# isolated_io_booster_pack.net
KiCad netlist of a schematic drawn in EAGLE
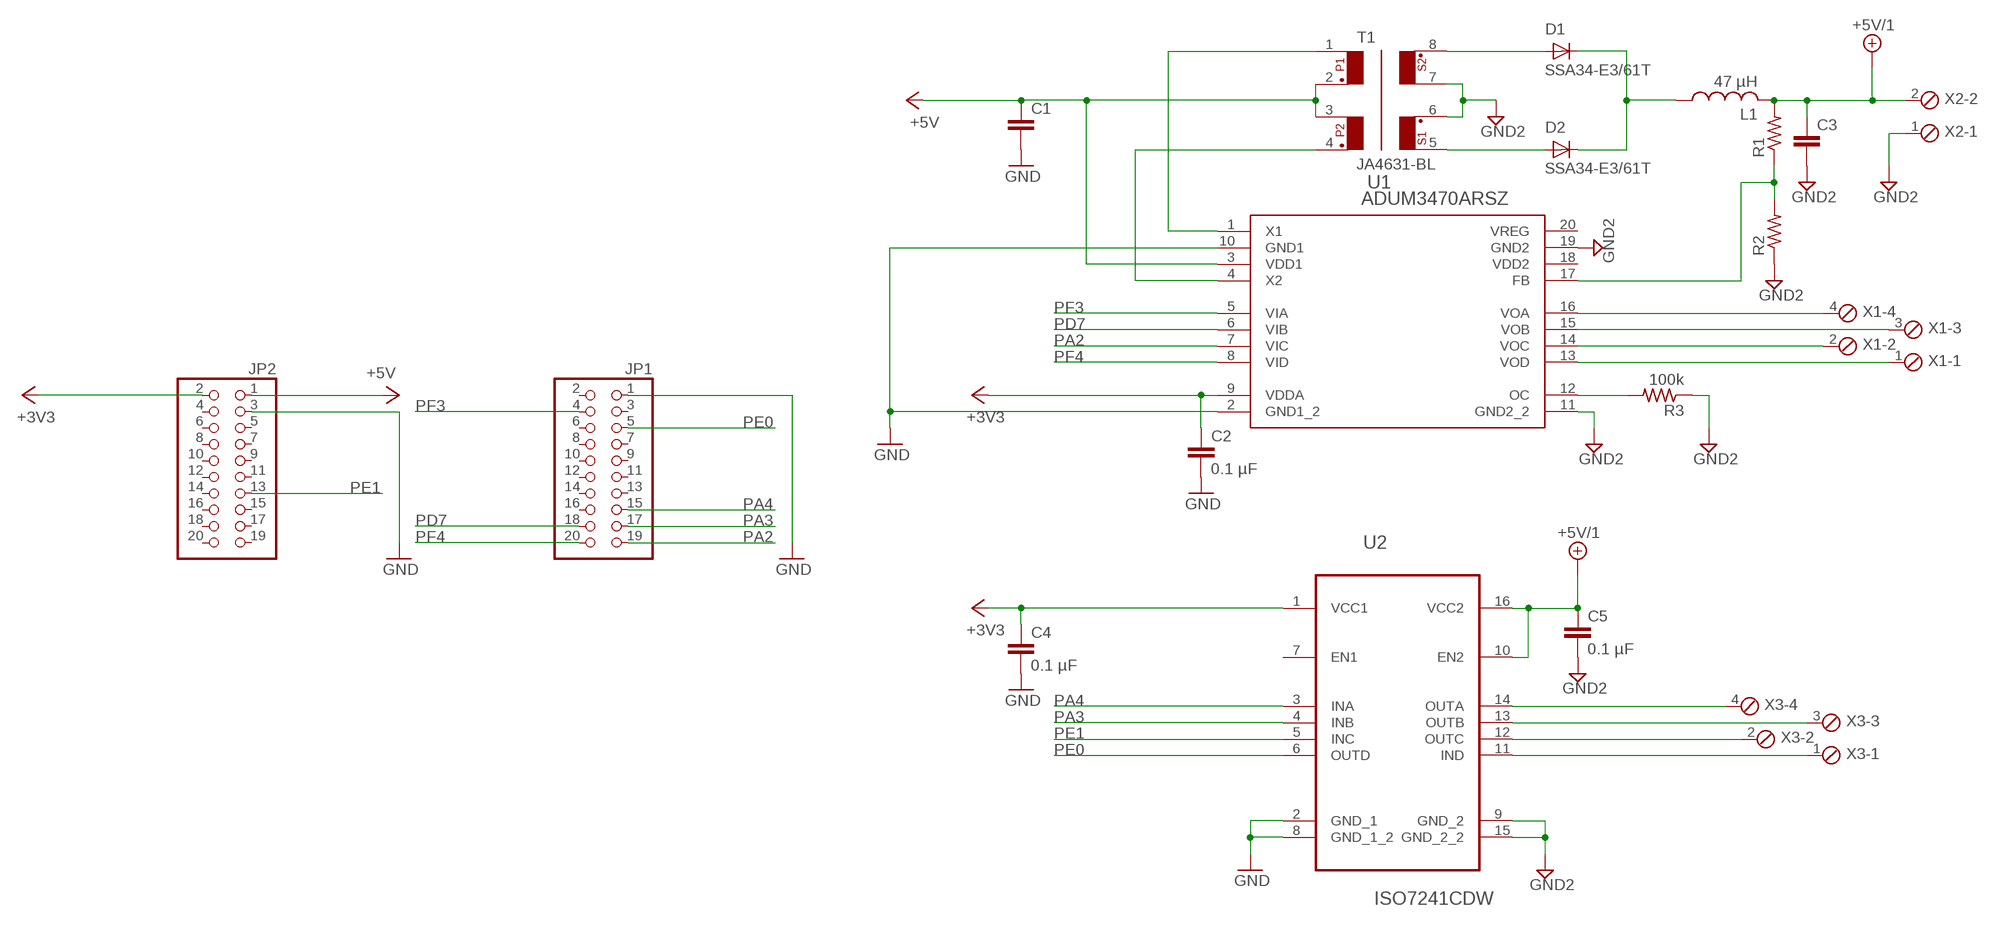
[diagram p0: schematic, sheet 1]

(export (version "E")
  (design (tool "Eeschema 10.0.6"))
  (components
    (comp (ref "C1")
      (value "C-EUC1210")
      (footprint "eagle-import:C1210")
      (libsource (lib "eagle-import") (part "C-EUC1210"))
    )
    (comp (ref "C2")
      (value "0.1 µF")
      (footprint "eagle-import:C0805")
      (libsource (lib "eagle-import") (part "C-EUC0805"))
    )
    (comp (ref "C3")
      (value "C-EUC1210")
      (footprint "eagle-import:C1210")
      (libsource (lib "eagle-import") (part "C-EUC1210"))
    )
    (comp (ref "C4")
      (value "0.1 µF")
      (footprint "eagle-import:C0805")
      (libsource (lib "eagle-import") (part "C-EUC0805"))
    )
    (comp (ref "C5")
      (value "0.1 µF")
      (footprint "eagle-import:C0805")
      (libsource (lib "eagle-import") (part "C-EUC0805"))
    )
    (comp (ref "D1")
      (value "SSA34-E3/61T")
      (footprint "eagle-import:SMA-DO214AC")
      (libsource (lib "eagle-import") (part "GF1"))
    )
    (comp (ref "D2")
      (value "SSA34-E3/61T")
      (footprint "eagle-import:SMA-DO214AC")
      (libsource (lib "eagle-import") (part "GF1"))
    )
    (comp (ref "JP1")
      (value "PINHD-2X10")
      (footprint "eagle-import:2X10")
      (libsource (lib "eagle-import") (part "PINHD-2X10"))
    )
    (comp (ref "JP2")
      (value "PINHD-2X10")
      (footprint "eagle-import:2X10")
      (libsource (lib "eagle-import") (part "PINHD-2X10"))
    )
    (comp (ref "L1")
      (value "47 µH")
      (footprint "eagle-import:LPS5030")
      (libsource (lib "eagle-import") (part "L-USLPS5030"))
    )
    (comp (ref "R1")
      (value "R-US_R0805")
      (footprint "eagle-import:R0805")
      (libsource (lib "eagle-import") (part "R-US_R0805"))
    )
    (comp (ref "R2")
      (value "R-US_R0805")
      (footprint "eagle-import:R0805")
      (libsource (lib "eagle-import") (part "R-US_R0805"))
    )
    (comp (ref "R3")
      (value "100k")
      (footprint "eagle-import:R0805")
      (libsource (lib "eagle-import") (part "R-US_R0805"))
    )
    (comp (ref "T1")
      (value "JA4631-BL")
      (footprint "eagle-import:JA4631-BL")
      (libsource (lib "eagle-import") (part "JA4631-BL"))
    )
    (comp (ref "U1")
      (value "ADUM3470ARSZ")
      (footprint "eagle-import:RS_20")
      (libsource (lib "eagle-import") (part "ADUM3470ARSZ"))
    )
    (comp (ref "U2")
      (value "ISO7241CDW")
      (footprint "eagle-import:SOIC127P1030X265-16N")
      (libsource (lib "eagle-import") (part "ISO7241CDW"))
    )
    (comp (ref "X1")
      (value "MPT4")
      (footprint "eagle-import:4POL254")
      (libsource (lib "eagle-import") (part "MPT4"))
    )
    (comp (ref "X2")
      (value "MPT2")
      (footprint "eagle-import:2POL254")
      (libsource (lib "eagle-import") (part "MPT2"))
    )
    (comp (ref "X3")
      (value "MPT4")
      (footprint "eagle-import:4POL254")
      (libsource (lib "eagle-import") (part "MPT4"))
    )
  )
  (nets
    (net (code "1") (name "+3V3") (class "Default")
      (node (ref "C2") (pin "1") (pinfunction "1_1") (pintype "passive"))
      (node (ref "C4") (pin "1") (pinfunction "1_1") (pintype "passive"))
      (node (ref "JP2") (pin "2") (pinfunction "2_2") (pintype "passive"))
      (node (ref "U1") (pin "9") (pinfunction "VDDA_9") (pintype "passive"))
      (node (ref "U2") (pin "1") (pinfunction "VCC1_1") (pintype "power_in"))
    )
    (net (code "2") (name "+5V") (class "Default")
      (node (ref "C1") (pin "1") (pinfunction "1_1") (pintype "passive"))
      (node (ref "JP2") (pin "1") (pinfunction "1_1") (pintype "passive"))
      (node (ref "T1") (pin "2") (pinfunction "2_2") (pintype "passive"))
      (node (ref "T1") (pin "3") (pinfunction "3_3") (pintype "passive"))
      (node (ref "U1") (pin "3") (pinfunction "VDD1_3") (pintype "passive"))
    )
    (net (code "3") (name "+5V{slash}1") (class "Default")
      (node (ref "C3") (pin "1") (pinfunction "1_1") (pintype "passive"))
      (node (ref "C5") (pin "1") (pinfunction "1_1") (pintype "passive"))
      (node (ref "L1") (pin "2") (pinfunction "2_2") (pintype "passive"))
      (node (ref "R1") (pin "2") (pinfunction "2_2") (pintype "passive"))
      (node (ref "U2") (pin "10") (pinfunction "EN2_10") (pintype "input"))
      (node (ref "U2") (pin "16") (pinfunction "VCC2_16") (pintype "power_in"))
      (node (ref "X2") (pin "2") (pinfunction "1_2") (pintype "passive"))
    )
    (net (code "4") (name "/PA2") (class "Default")
      (node (ref "JP1") (pin "19") (pinfunction "19_19") (pintype "passive"))
      (node (ref "U1") (pin "7") (pinfunction "VIC_7") (pintype "passive"))
    )
    (net (code "5") (name "/PA3") (class "Default")
      (node (ref "JP1") (pin "17") (pinfunction "17_17") (pintype "passive"))
      (node (ref "U2") (pin "4") (pinfunction "INB_4") (pintype "input"))
    )
    (net (code "6") (name "/PA4") (class "Default")
      (node (ref "JP1") (pin "15") (pinfunction "15_15") (pintype "passive"))
      (node (ref "U2") (pin "3") (pinfunction "INA_3") (pintype "input"))
    )
    (net (code "7") (name "/PD7") (class "Default")
      (node (ref "JP1") (pin "18") (pinfunction "18_18") (pintype "passive"))
      (node (ref "U1") (pin "6") (pinfunction "VIB_6") (pintype "passive"))
    )
    (net (code "8") (name "/PE0") (class "Default")
      (node (ref "JP1") (pin "5") (pinfunction "5_5") (pintype "passive"))
      (node (ref "U2") (pin "6") (pinfunction "OUTD_6") (pintype "output"))
    )
    (net (code "9") (name "/PE1") (class "Default")
      (node (ref "JP2") (pin "13") (pinfunction "13_13") (pintype "passive"))
      (node (ref "U2") (pin "5") (pinfunction "INC_5") (pintype "input"))
    )
    (net (code "10") (name "/PF3") (class "Default")
      (node (ref "JP1") (pin "4") (pinfunction "4_4") (pintype "passive"))
      (node (ref "U1") (pin "5") (pinfunction "VIA_5") (pintype "passive"))
    )
    (net (code "11") (name "/PF4") (class "Default")
      (node (ref "JP1") (pin "20") (pinfunction "20_20") (pintype "passive"))
      (node (ref "U1") (pin "8") (pinfunction "VID_8") (pintype "passive"))
    )
    (net (code "12") (name "GND") (class "Default")
      (node (ref "C1") (pin "2") (pinfunction "2_2") (pintype "passive"))
      (node (ref "C2") (pin "2") (pinfunction "2_2") (pintype "passive"))
      (node (ref "C4") (pin "2") (pinfunction "2_2") (pintype "passive"))
      (node (ref "JP1") (pin "1") (pinfunction "1_1") (pintype "passive"))
      (node (ref "JP2") (pin "3") (pinfunction "3_3") (pintype "passive"))
      (node (ref "U1") (pin "10") (pinfunction "GND1_10") (pintype "passive"))
      (node (ref "U1") (pin "2") (pinfunction "GND1_2_2") (pintype "passive"))
      (node (ref "U2") (pin "2") (pinfunction "GND_1_2") (pintype "passive"))
      (node (ref "U2") (pin "8") (pinfunction "GND_1_2_8") (pintype "passive"))
    )
    (net (code "13") (name "GND2") (class "Default")
      (node (ref "C3") (pin "2") (pinfunction "2_2") (pintype "passive"))
      (node (ref "C5") (pin "2") (pinfunction "2_2") (pintype "passive"))
      (node (ref "R2") (pin "1") (pinfunction "1_1") (pintype "passive"))
      (node (ref "R3") (pin "1") (pinfunction "1_1") (pintype "passive"))
      (node (ref "T1") (pin "6") (pinfunction "6_6") (pintype "passive"))
      (node (ref "T1") (pin "7") (pinfunction "7_7") (pintype "passive"))
      (node (ref "U1") (pin "11") (pinfunction "GND2_2_11") (pintype "passive"))
      (node (ref "U1") (pin "19") (pinfunction "GND2_19") (pintype "passive"))
      (node (ref "U2") (pin "15") (pinfunction "GND_2_2_15") (pintype "passive"))
      (node (ref "U2") (pin "9") (pinfunction "GND_2_9") (pintype "passive"))
      (node (ref "X2") (pin "1") (pinfunction "1_1") (pintype "passive"))
    )
    (net (code "14") (name "Net-(D1-C)") (class "Default")
      (node (ref "D1") (pin "K") (pinfunction "C_K") (pintype "passive"))
      (node (ref "D2") (pin "K") (pinfunction "C_K") (pintype "passive"))
      (node (ref "L1") (pin "1") (pinfunction "1_1") (pintype "passive"))
    )
    (net (code "15") (name "Net-(D1-PadA)") (class "Default")
      (node (ref "D1") (pin "A") (pinfunction "A_A") (pintype "passive"))
      (node (ref "T1") (pin "8") (pinfunction "8_8") (pintype "passive"))
    )
    (net (code "16") (name "Net-(D2-PadA)") (class "Default")
      (node (ref "D2") (pin "A") (pinfunction "A_A") (pintype "passive"))
      (node (ref "T1") (pin "5") (pinfunction "5_5") (pintype "passive"))
    )
    (net (code "17") (name "Net-(U1-FB)") (class "Default")
      (node (ref "R1") (pin "1") (pinfunction "1_1") (pintype "passive"))
      (node (ref "R2") (pin "2") (pinfunction "2_2") (pintype "passive"))
      (node (ref "U1") (pin "17") (pinfunction "FB_17") (pintype "passive"))
    )
    (net (code "18") (name "Net-(U1-OC)") (class "Default")
      (node (ref "R3") (pin "2") (pinfunction "2_2") (pintype "passive"))
      (node (ref "U1") (pin "12") (pinfunction "OC_12") (pintype "passive"))
    )
    (net (code "19") (name "Net-(U1-VOA)") (class "Default")
      (node (ref "U1") (pin "16") (pinfunction "VOA_16") (pintype "passive"))
      (node (ref "X1") (pin "4") (pinfunction "1_4") (pintype "passive"))
    )
    (net (code "20") (name "Net-(U1-VOB)") (class "Default")
      (node (ref "U1") (pin "15") (pinfunction "VOB_15") (pintype "passive"))
      (node (ref "X1") (pin "3") (pinfunction "1_3") (pintype "passive"))
    )
    (net (code "21") (name "Net-(U1-VOC)") (class "Default")
      (node (ref "U1") (pin "14") (pinfunction "VOC_14") (pintype "passive"))
      (node (ref "X1") (pin "2") (pinfunction "1_2") (pintype "passive"))
    )
    (net (code "22") (name "Net-(U1-VOD)") (class "Default")
      (node (ref "U1") (pin "13") (pinfunction "VOD_13") (pintype "passive"))
      (node (ref "X1") (pin "1") (pinfunction "1_1") (pintype "passive"))
    )
    (net (code "23") (name "Net-(U1-X1)") (class "Default")
      (node (ref "T1") (pin "1") (pinfunction "1_1") (pintype "passive"))
      (node (ref "U1") (pin "1") (pinfunction "X1_1") (pintype "passive"))
    )
    (net (code "24") (name "Net-(U1-X2)") (class "Default")
      (node (ref "T1") (pin "4") (pinfunction "4_4") (pintype "passive"))
      (node (ref "U1") (pin "4") (pinfunction "X2_4") (pintype "passive"))
    )
    (net (code "25") (name "Net-(U2-IND)") (class "Default")
      (node (ref "U2") (pin "11") (pinfunction "IND_11") (pintype "input"))
      (node (ref "X3") (pin "1") (pinfunction "1_1") (pintype "passive"))
    )
    (net (code "26") (name "Net-(U2-OUTA)") (class "Default")
      (node (ref "U2") (pin "14") (pinfunction "OUTA_14") (pintype "output"))
      (node (ref "X3") (pin "4") (pinfunction "1_4") (pintype "passive"))
    )
    (net (code "27") (name "Net-(U2-OUTB)") (class "Default")
      (node (ref "U2") (pin "13") (pinfunction "OUTB_13") (pintype "output"))
      (node (ref "X3") (pin "3") (pinfunction "1_3") (pintype "passive"))
    )
    (net (code "28") (name "Net-(U2-OUTC)") (class "Default")
      (node (ref "U2") (pin "12") (pinfunction "OUTC_12") (pintype "output"))
      (node (ref "X3") (pin "2") (pinfunction "1_2") (pintype "passive"))
    )
    (net (code "29") (name "unconnected-(JP1-Pad2)") (class "Default")
      (node (ref "JP1") (pin "2") (pinfunction "2_2") (pintype "passive"))
    )
    (net (code "30") (name "unconnected-(JP1-Pad3)") (class "Default")
      (node (ref "JP1") (pin "3") (pinfunction "3_3") (pintype "passive"))
    )
    (net (code "31") (name "unconnected-(JP1-Pad6)") (class "Default")
      (node (ref "JP1") (pin "6") (pinfunction "6_6") (pintype "passive"))
    )
    (net (code "32") (name "unconnected-(JP1-Pad7)") (class "Default")
      (node (ref "JP1") (pin "7") (pinfunction "7_7") (pintype "passive"))
    )
    (net (code "33") (name "unconnected-(JP1-Pad8)") (class "Default")
      (node (ref "JP1") (pin "8") (pinfunction "8_8") (pintype "passive"))
    )
    (net (code "34") (name "unconnected-(JP1-Pad9)") (class "Default")
      (node (ref "JP1") (pin "9") (pinfunction "9_9") (pintype "passive"))
    )
    (net (code "35") (name "unconnected-(JP1-Pad10)") (class "Default")
      (node (ref "JP1") (pin "10") (pinfunction "10_10") (pintype "passive"))
    )
    (net (code "36") (name "unconnected-(JP1-Pad11)") (class "Default")
      (node (ref "JP1") (pin "11") (pinfunction "11_11") (pintype "passive"))
    )
    (net (code "37") (name "unconnected-(JP1-Pad12)") (class "Default")
      (node (ref "JP1") (pin "12") (pinfunction "12_12") (pintype "passive"))
    )
    (net (code "38") (name "unconnected-(JP1-Pad13)") (class "Default")
      (node (ref "JP1") (pin "13") (pinfunction "13_13") (pintype "passive"))
    )
    (net (code "39") (name "unconnected-(JP1-Pad14)") (class "Default")
      (node (ref "JP1") (pin "14") (pinfunction "14_14") (pintype "passive"))
    )
    (net (code "40") (name "unconnected-(JP1-Pad16)") (class "Default")
      (node (ref "JP1") (pin "16") (pinfunction "16_16") (pintype "passive"))
    )
    (net (code "41") (name "unconnected-(JP2-Pad4)") (class "Default")
      (node (ref "JP2") (pin "4") (pinfunction "4_4") (pintype "passive"))
    )
    (net (code "42") (name "unconnected-(JP2-Pad5)") (class "Default")
      (node (ref "JP2") (pin "5") (pinfunction "5_5") (pintype "passive"))
    )
    (net (code "43") (name "unconnected-(JP2-Pad6)") (class "Default")
      (node (ref "JP2") (pin "6") (pinfunction "6_6") (pintype "passive"))
    )
    (net (code "44") (name "unconnected-(JP2-Pad7)") (class "Default")
      (node (ref "JP2") (pin "7") (pinfunction "7_7") (pintype "passive"))
    )
    (net (code "45") (name "unconnected-(JP2-Pad8)") (class "Default")
      (node (ref "JP2") (pin "8") (pinfunction "8_8") (pintype "passive"))
    )
    (net (code "46") (name "unconnected-(JP2-Pad9)") (class "Default")
      (node (ref "JP2") (pin "9") (pinfunction "9_9") (pintype "passive"))
    )
    (net (code "47") (name "unconnected-(JP2-Pad10)") (class "Default")
      (node (ref "JP2") (pin "10") (pinfunction "10_10") (pintype "passive"))
    )
    (net (code "48") (name "unconnected-(JP2-Pad11)") (class "Default")
      (node (ref "JP2") (pin "11") (pinfunction "11_11") (pintype "passive"))
    )
    (net (code "49") (name "unconnected-(JP2-Pad12)") (class "Default")
      (node (ref "JP2") (pin "12") (pinfunction "12_12") (pintype "passive"))
    )
    (net (code "50") (name "unconnected-(JP2-Pad14)") (class "Default")
      (node (ref "JP2") (pin "14") (pinfunction "14_14") (pintype "passive"))
    )
    (net (code "51") (name "unconnected-(JP2-Pad15)") (class "Default")
      (node (ref "JP2") (pin "15") (pinfunction "15_15") (pintype "passive"))
    )
    (net (code "52") (name "unconnected-(JP2-Pad16)") (class "Default")
      (node (ref "JP2") (pin "16") (pinfunction "16_16") (pintype "passive"))
    )
    (net (code "53") (name "unconnected-(JP2-Pad17)") (class "Default")
      (node (ref "JP2") (pin "17") (pinfunction "17_17") (pintype "passive"))
    )
    (net (code "54") (name "unconnected-(JP2-Pad18)") (class "Default")
      (node (ref "JP2") (pin "18") (pinfunction "18_18") (pintype "passive"))
    )
    (net (code "55") (name "unconnected-(JP2-Pad19)") (class "Default")
      (node (ref "JP2") (pin "19") (pinfunction "19_19") (pintype "passive"))
    )
    (net (code "56") (name "unconnected-(JP2-Pad20)") (class "Default")
      (node (ref "JP2") (pin "20") (pinfunction "20_20") (pintype "passive"))
    )
    (net (code "57") (name "unconnected-(U1-VDD2-Pad18)") (class "Default")
      (node (ref "U1") (pin "18") (pinfunction "VDD2_18") (pintype "passive"))
    )
    (net (code "58") (name "unconnected-(U1-VREG-Pad20)") (class "Default")
      (node (ref "U1") (pin "20") (pinfunction "VREG_20") (pintype "passive"))
    )
    (net (code "59") (name "unconnected-(U2-EN1-Pad7)") (class "Default")
      (node (ref "U2") (pin "7") (pinfunction "EN1_7") (pintype "input"))
    )
  )
)
